# Uni-2_4.net
KiCad netlist of a schematic drawn in EAGLE
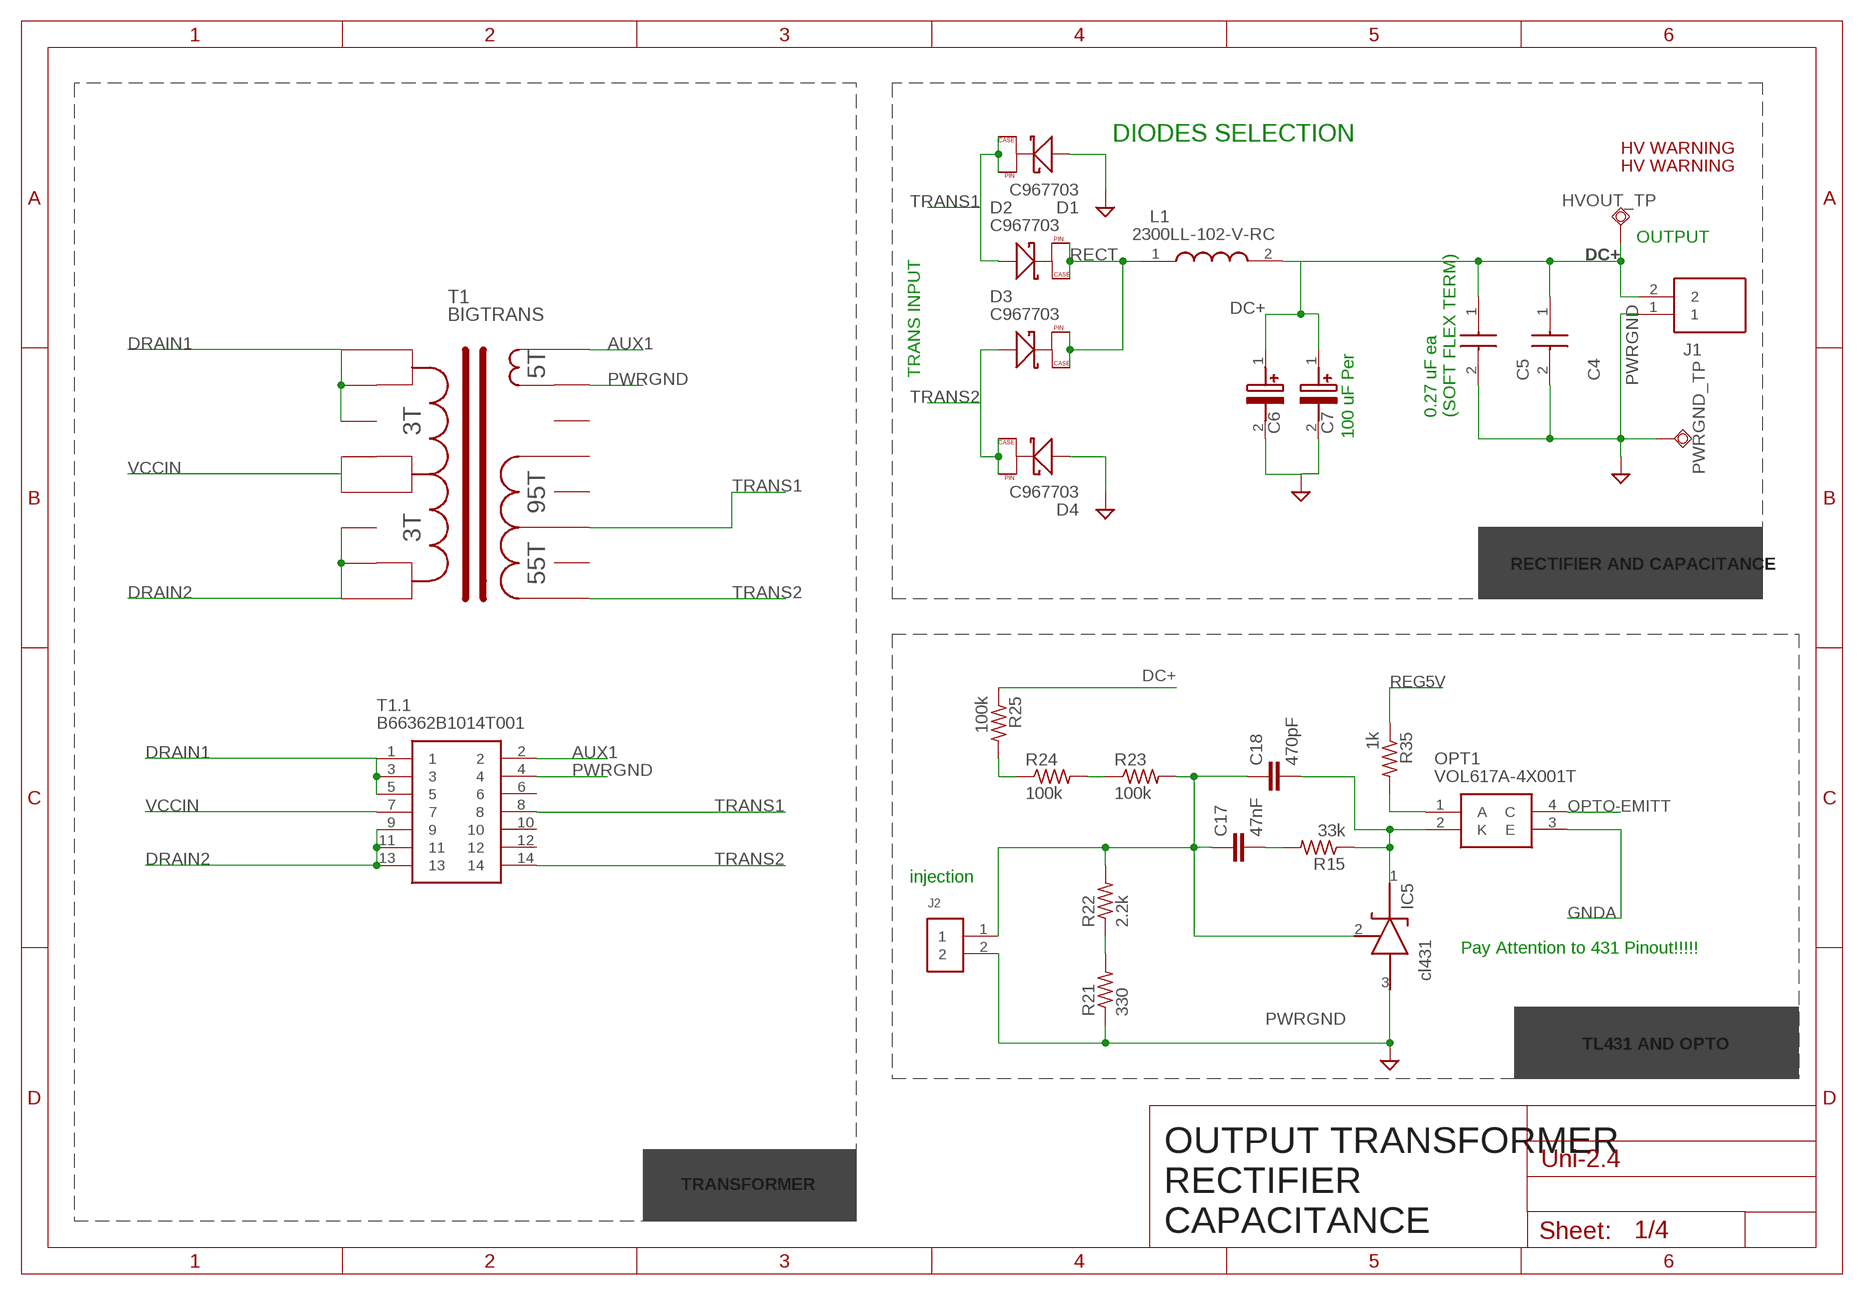
[diagram p0: schematic, sheet 1]
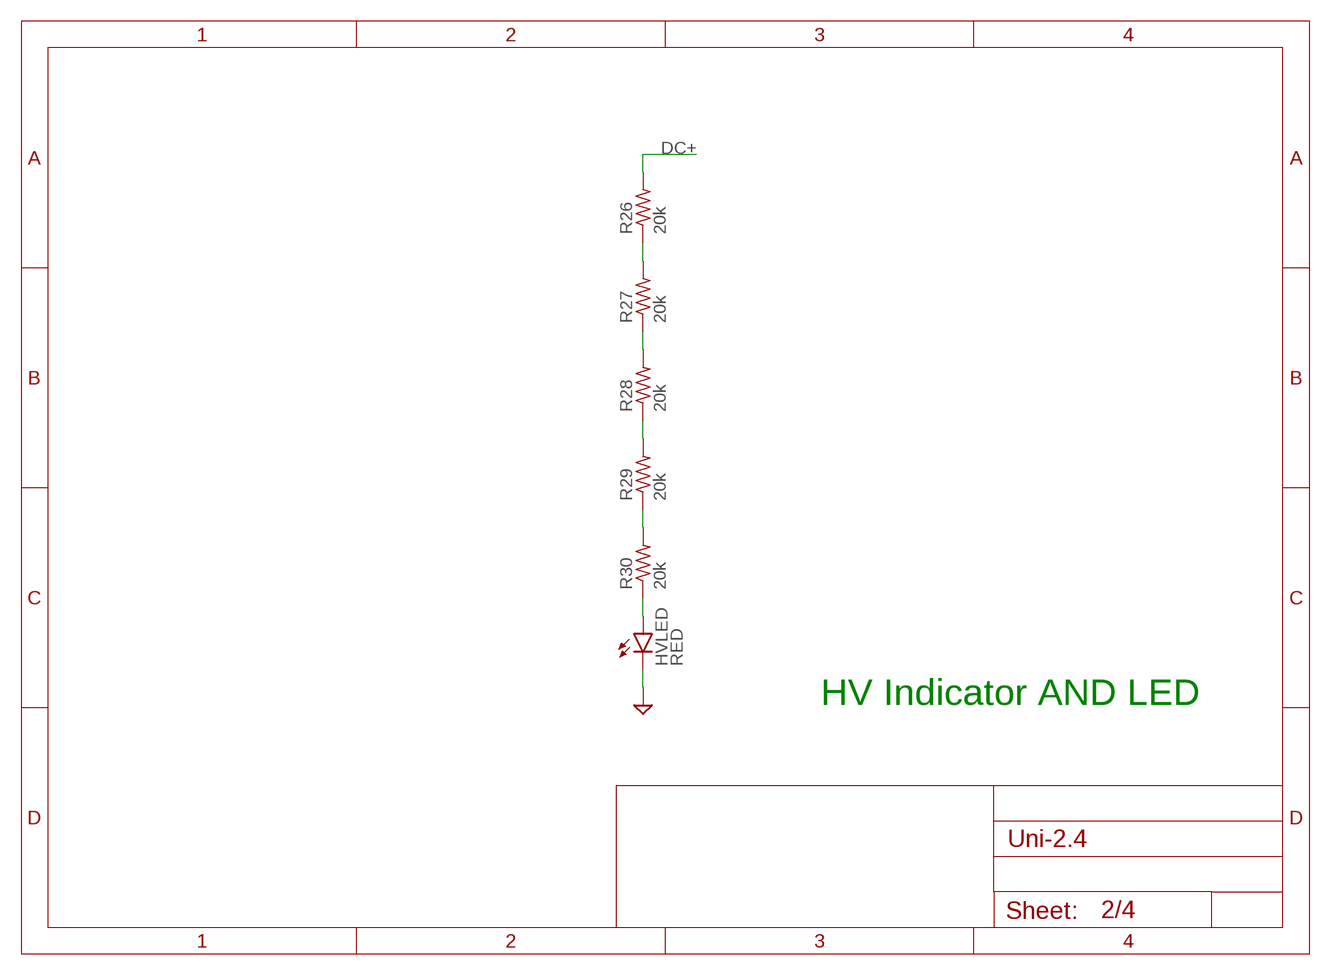
[diagram p1: schematic, sheet 2]
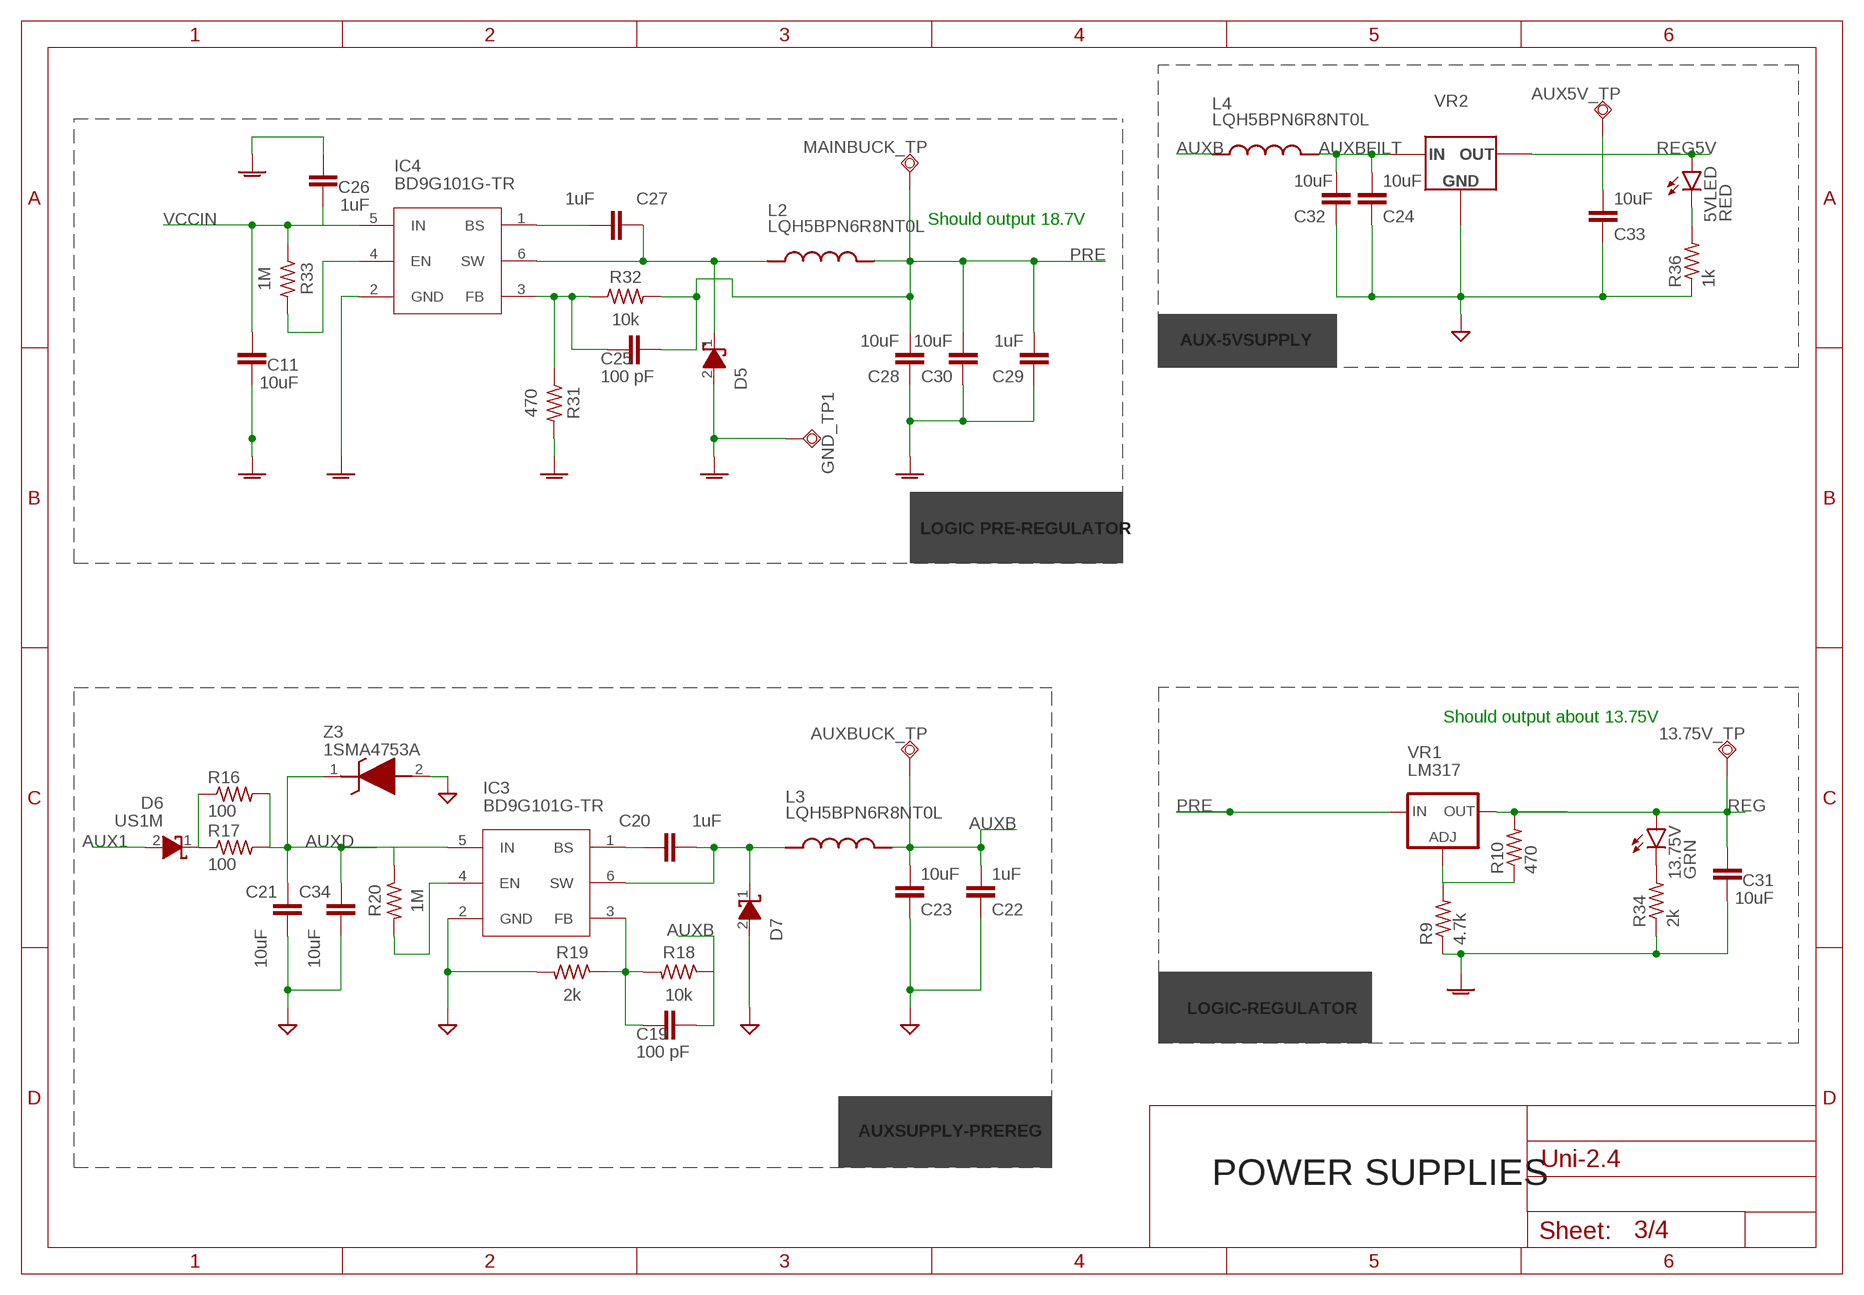
[diagram p2: schematic, sheet 3]
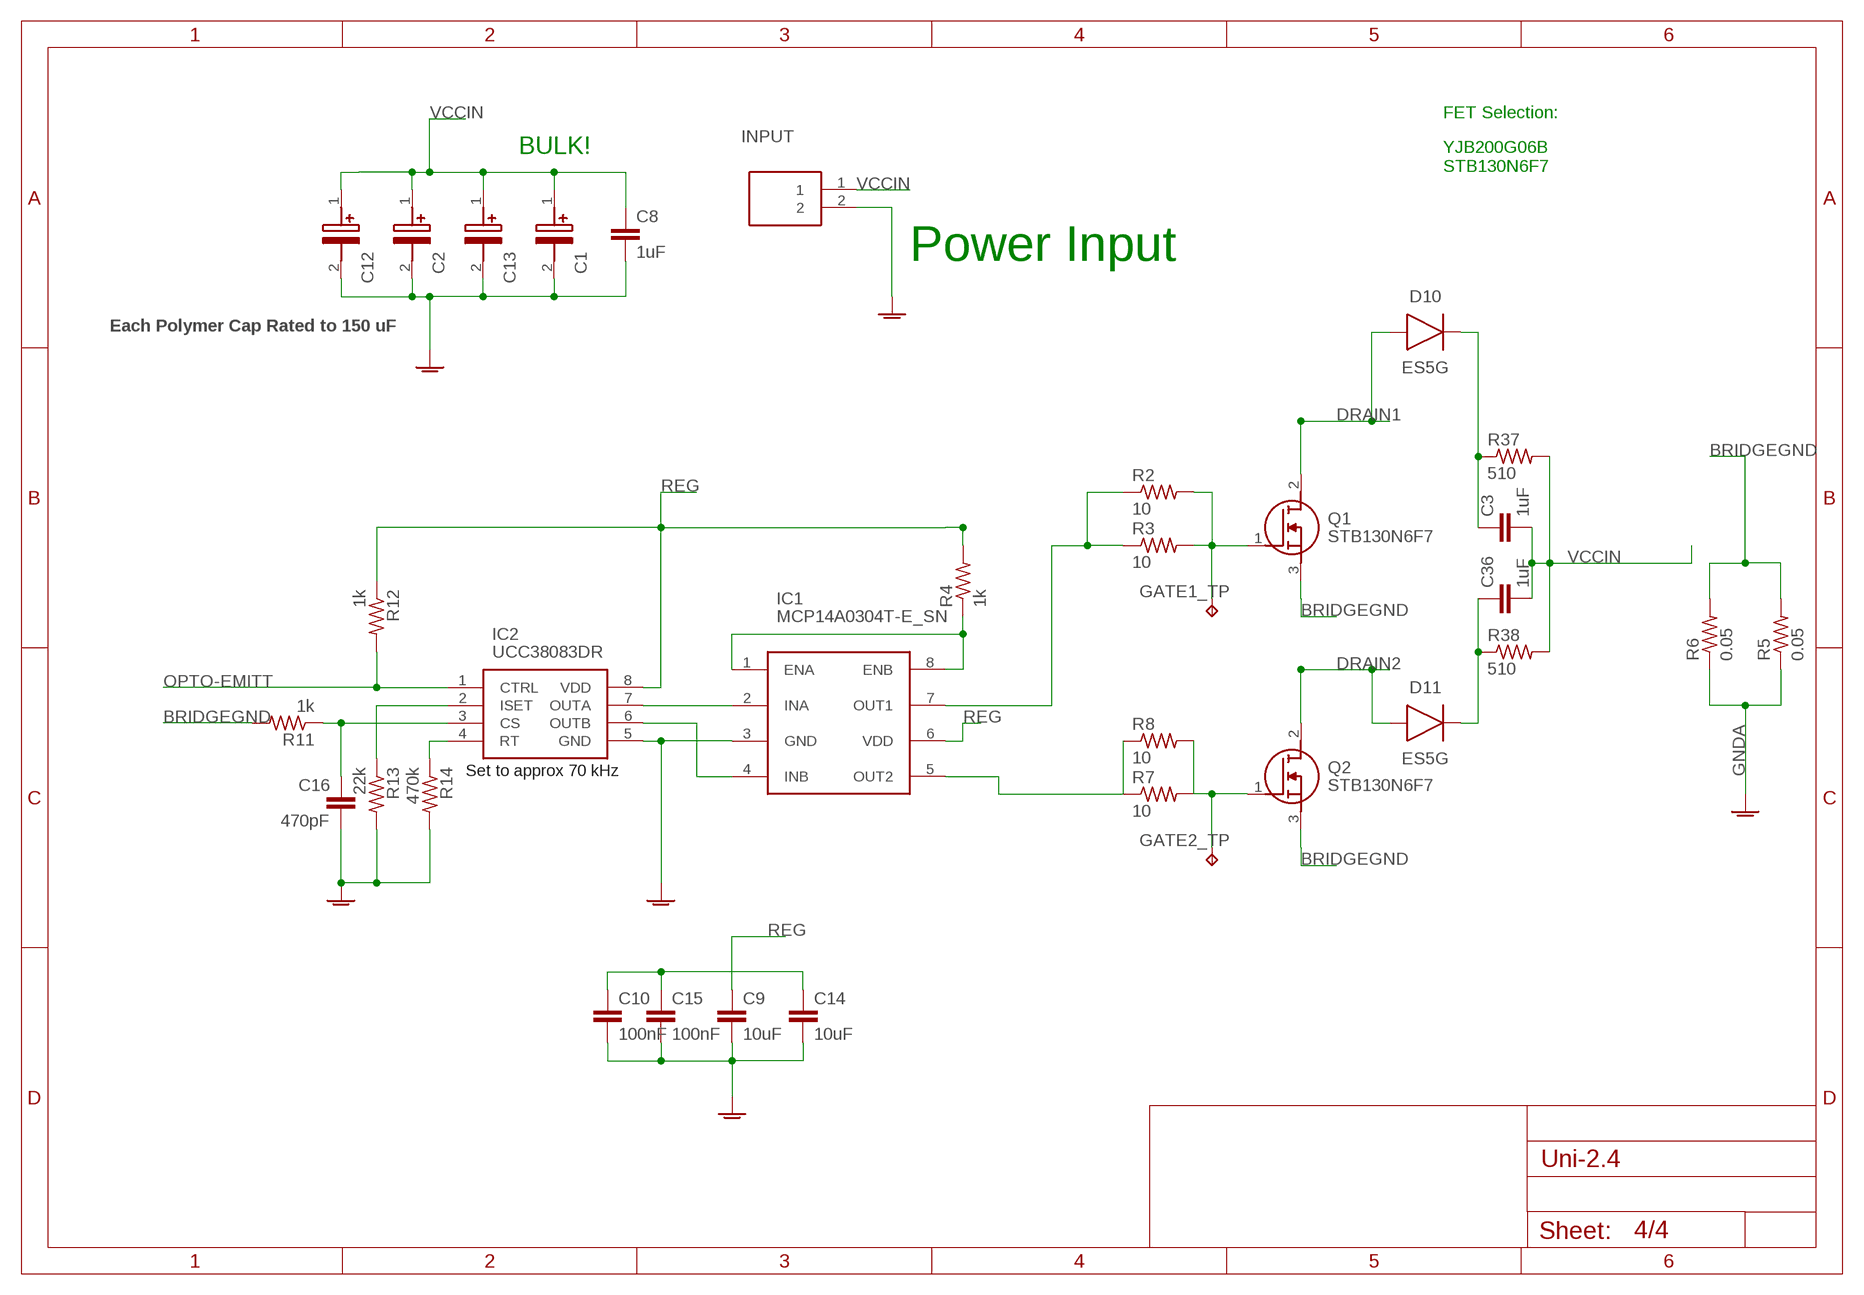
[diagram p3: schematic, sheet 4]

(export (version "E")
  (design (tool "Eeschema 10.0.6"))
  (components
    (comp (ref "HVLED")
      (value "RED")
      (footprint "eagle-import:CHIPLED_0805")
      (libsource (lib "eagle-import") (part "LEDCHIPLED_0805"))
    )
    (comp (ref "R26")
      (value "20k")
      (footprint "eagle-import:R1206")
      (libsource (lib "eagle-import") (part "R-US_R1206"))
    )
    (comp (ref "R27")
      (value "20k")
      (footprint "eagle-import:R1206")
      (libsource (lib "eagle-import") (part "R-US_R1206"))
    )
    (comp (ref "R28")
      (value "20k")
      (footprint "eagle-import:R1206")
      (libsource (lib "eagle-import") (part "R-US_R1206"))
    )
    (comp (ref "R29")
      (value "20k")
      (footprint "eagle-import:R1206")
      (libsource (lib "eagle-import") (part "R-US_R1206"))
    )
    (comp (ref "R30")
      (value "20k")
      (footprint "eagle-import:R1206")
      (libsource (lib "eagle-import") (part "R-US_R1206"))
    )
    (comp (ref "C4")
      (value "C1812C274KCRACAUTO")
      (footprint "eagle-import:C1812")
      (fields (field (name "MOUSER_PART_NUMBER") "80-C1812C274KCRAUTO"))
      (libsource (lib "eagle-import") (part "C1812C274KCRACAUTO"))
    )
    (comp (ref "C5")
      (value "C1812C274KCRACAUTO")
      (footprint "eagle-import:C1812")
      (fields (field (name "MOUSER_PART_NUMBER") "80-C1812C274KCRAUTO"))
      (libsource (lib "eagle-import") (part "C1812C274KCRACAUTO"))
    )
    (comp (ref "C6")
      (value "400BXW100MEFR18X25")
      (footprint "eagle-import:CAPPRD750W80D1825H2700")
      (libsource (lib "eagle-import") (part "400BXW100MEFR18X25"))
    )
    (comp (ref "C7")
      (value "400BXW100MEFR18X25")
      (footprint "eagle-import:CAPPRD750W80D1825H2700")
      (libsource (lib "eagle-import") (part "400BXW100MEFR18X25"))
    )
    (comp (ref "C17")
      (value "47nF")
      (footprint "eagle-import:C0603K")
      (libsource (lib "eagle-import") (part "rcl_334_C-EUC0603K"))
    )
    (comp (ref "C18")
      (value "470pF")
      (footprint "eagle-import:C0603K")
      (libsource (lib "eagle-import") (part "rcl_334_C-EUC0603K"))
    )
    (comp (ref "D1")
      (value "C967703")
      (footprint "eagle-import:TO-252")
      (libsource (lib "eagle-import") (part "SICDIODE"))
    )
    (comp (ref "D2")
      (value "C967703")
      (footprint "eagle-import:TO-252")
      (libsource (lib "eagle-import") (part "SICDIODE"))
    )
    (comp (ref "D3")
      (value "C967703")
      (footprint "eagle-import:TO-252")
      (libsource (lib "eagle-import") (part "SICDIODE"))
    )
    (comp (ref "D4")
      (value "C967703")
      (footprint "eagle-import:TO-252")
      (libsource (lib "eagle-import") (part "SICDIODE"))
    )
    (comp (ref "HVOUT_TP")
      (value "TPSQPAD1-13")
      (footprint "eagle-import:P1-13")
      (libsource (lib "eagle-import") (part "TPSQPAD1-13"))
    )
    (comp (ref "IC5")
      (value "cl431")
      (footprint "eagle-import:SOT95P280X145-3N")
      (fields
        (field (name "MANUFACTURER_PART_NUMBER") "TL431CL3T")
        (field (name "MOUSER_PART_NUMBER") "511-TL431CL3T")
      )
      (libsource (lib "eagle-import") (part "TL431CL3T"))
    )
    (comp (ref "J1")
      (value "TB005-762-02BE")
      (footprint "eagle-import:TB00576202BE")
      (fields (field (name "MOUSER_PART_NUMBER") "490-TB005-762-02BE"))
      (libsource (lib "eagle-import") (part "TB005-762-02BE"))
    )
    (comp (ref "J2")
      (value "61300211121")
      (footprint "eagle-import:61300211121")
      (fields
        (field (name "DIGI_KEY_PART_NUMBER") "732-5315-ND")
        (field (name "MANUFACTURER") "Wurth Electronics Inc.")
        (field (name "CREATED_BY") "PCBLayout.com")
      )
      (libsource (lib "eagle-import") (part "61300211121"))
    )
    (comp (ref "L1")
      (value "2300LL-102-V-RC")
      (footprint "eagle-import:2300LL102VRC")
      (fields (field (name "MOUSER_PART_NUMBER") "652-2300LL-102-V-RC"))
      (libsource (lib "eagle-import") (part "2300LL-102-V-RC"))
    )
    (comp (ref "OPT1")
      (value "VOL617A-4X001T")
      (footprint "eagle-import:SOP254P1015X230-4N")
      (fields (field (name "MOUSER_PART_NUMBER") "78-VOL617A-4X001T"))
      (libsource (lib "eagle-import") (part "VOL617A-4X001T"))
    )
    (comp (ref "PWRGND_TP")
      (value "TPSQPAD1-13")
      (footprint "eagle-import:P1-13")
      (libsource (lib "eagle-import") (part "TPSQPAD1-13"))
    )
    (comp (ref "R15")
      (value "33k")
      (footprint "eagle-import:R0603")
      (libsource (lib "eagle-import") (part "R-US_R0603"))
    )
    (comp (ref "R21")
      (value "330")
      (footprint "eagle-import:R0805")
      (libsource (lib "eagle-import") (part "R-US_R0805"))
    )
    (comp (ref "R22")
      (value "2.2k")
      (footprint "eagle-import:R0805")
      (libsource (lib "eagle-import") (part "R-US_R0805"))
    )
    (comp (ref "R23")
      (value "100k")
      (footprint "eagle-import:R1206")
      (libsource (lib "eagle-import") (part "R-US_R1206"))
    )
    (comp (ref "R24")
      (value "100k")
      (footprint "eagle-import:R1206")
      (libsource (lib "eagle-import") (part "R-US_R1206"))
    )
    (comp (ref "R25")
      (value "100k")
      (footprint "eagle-import:R1206")
      (libsource (lib "eagle-import") (part "R-US_R1206"))
    )
    (comp (ref "R35")
      (value "1k")
      (footprint "eagle-import:R0603")
      (libsource (lib "eagle-import") (part "R-US_R0603"))
    )
    (comp (ref "T1")
      (value "BIGTRANS")
      (footprint "eagle-import:BIGTRANS!")
      (libsource (lib "eagle-import") (part "BIGTRANS"))
    )
    (comp (ref "T1.1")
      (value "B66362B1014T001")
      (footprint "eagle-import:B66362B1014T001")
      (fields (field (name "MOUSER_PART_NUMBER") "871-B66362B1014T001"))
      (libsource (lib "eagle-import") (part "B66362B1014T001"))
    )
    (comp (ref "U$3")
      (value "HV")
      (footprint "eagle-import:PSFBC_ELECTRIC_SHOCK")
      (libsource (lib "eagle-import") (part "HV"))
    )
    (comp (ref "U$4")
      (value "HV")
      (footprint "eagle-import:PSFBC_ELECTRIC_SHOCK")
      (libsource (lib "eagle-import") (part "HV"))
    )
    (comp (ref "5VLED")
      (value "RED")
      (footprint "eagle-import:CHIPLED_0805")
      (fields (field (name "LCSC_PART") "C72043"))
      (libsource (lib "eagle-import") (part "LEDCHIPLED_0805"))
    )
    (comp (ref "13.75V")
      (value "GRN")
      (footprint "eagle-import:CHIPLED_0805")
      (fields (field (name "LCSC_PART") "C72043"))
      (libsource (lib "eagle-import") (part "LEDCHIPLED_0805"))
    )
    (comp (ref "13.75V_TP")
      (value "TPSQPAD1-17")
      (footprint "eagle-import:P1-17")
      (libsource (lib "eagle-import") (part "TPSQPAD1-17"))
    )
    (comp (ref "AUX5V_TP")
      (value "TPSQPAD1-17")
      (footprint "eagle-import:P1-17")
      (libsource (lib "eagle-import") (part "TPSQPAD1-17"))
    )
    (comp (ref "AUXBUCK_TP")
      (value "TPSQPAD1-17")
      (footprint "eagle-import:P1-17")
      (libsource (lib "eagle-import") (part "TPSQPAD1-17"))
    )
    (comp (ref "C11")
      (value "10uF")
      (footprint "eagle-import:C0805K")
      (fields (field (name "LCSC_PART") "C440198"))
      (libsource (lib "eagle-import") (part "C-EUC0805K"))
    )
    (comp (ref "C19")
      (value "100 pF")
      (footprint "eagle-import:C0402K")
      (fields (field (name "LCSC_PART") "C1546"))
      (libsource (lib "eagle-import") (part "rcl_334_C-EUC0402K"))
    )
    (comp (ref "C20")
      (value "1uF")
      (footprint "eagle-import:C0603K")
      (fields (field (name "LCSC_PART") "C14663"))
      (libsource (lib "eagle-import") (part "rcl_334_C-EUC0603K"))
    )
    (comp (ref "C21")
      (value "10uF")
      (footprint "eagle-import:C0805K")
      (libsource (lib "eagle-import") (part "rcl_334_C-EUC0805K"))
    )
    (comp (ref "C22")
      (value "1uF")
      (footprint "eagle-import:C0402")
      (fields (field (name "LCSC_PART") "C440198"))
      (libsource (lib "eagle-import") (part "rcl_334_C-EUC0402"))
    )
    (comp (ref "C23")
      (value "10uF")
      (footprint "eagle-import:C0603K")
      (fields (field (name "LCSC_PART") "C440198"))
      (libsource (lib "eagle-import") (part "rcl_334_C-EUC0603K"))
    )
    (comp (ref "C24")
      (value "10uF")
      (footprint "eagle-import:C0603K")
      (fields (field (name "LCSC_PART") "C440198"))
      (libsource (lib "eagle-import") (part "rcl_334_C-EUC0603K"))
    )
    (comp (ref "C25")
      (value "100 pF")
      (footprint "eagle-import:C0402K")
      (fields (field (name "LCSC_PART") "C1546"))
      (libsource (lib "eagle-import") (part "rcl_334_C-EUC0402K"))
    )
    (comp (ref "C26")
      (value "1uF")
      (footprint "eagle-import:C0603K")
      (fields (field (name "LCSC_PART") "C440198"))
      (libsource (lib "eagle-import") (part "rcl_334_C-EUC0603K"))
    )
    (comp (ref "C27")
      (value "1uF")
      (footprint "eagle-import:C0603K")
      (fields (field (name "LCSC_PART") "C14663"))
      (libsource (lib "eagle-import") (part "rcl_334_C-EUC0603K"))
    )
    (comp (ref "C28")
      (value "10uF")
      (footprint "eagle-import:C0603K")
      (fields (field (name "LCSC_PART") "C440198"))
      (libsource (lib "eagle-import") (part "C-EUC0603K"))
    )
    (comp (ref "C29")
      (value "1uF")
      (footprint "eagle-import:C0603K")
      (fields (field (name "LCSC_PART") "C440198"))
      (libsource (lib "eagle-import") (part "C-EUC0603K"))
    )
    (comp (ref "C30")
      (value "10uF")
      (footprint "eagle-import:C0603K")
      (fields (field (name "LCSC_PART") "C440198"))
      (libsource (lib "eagle-import") (part "C-EUC0603K"))
    )
    (comp (ref "C31")
      (value "10uF")
      (footprint "eagle-import:C0603K")
      (fields (field (name "LCSC_PART") "C440198"))
      (libsource (lib "eagle-import") (part "C-EUC0603K"))
    )
    (comp (ref "C32")
      (value "10uF")
      (footprint "eagle-import:C0603K")
      (fields (field (name "LCSC_PART") "C440198"))
      (libsource (lib "eagle-import") (part "rcl_334_C-EUC0603K"))
    )
    (comp (ref "C33")
      (value "10uF")
      (footprint "eagle-import:C0603K")
      (libsource (lib "eagle-import") (part "rcl_334_C-EUC0603K"))
    )
    (comp (ref "C34")
      (value "10uF")
      (footprint "eagle-import:C0805K")
      (libsource (lib "eagle-import") (part "rcl_334_C-EUC0805K"))
    )
    (comp (ref "D5")
      (value "SCHOTTKY")
      (footprint "eagle-import:DIOM5127X229N")
      (fields
        (field (name "MANUFACTURER_PART_NUMBER") "SS16HE3_B/H")
        (field (name "MOUSER_PART_NUMBER") "78-SS16HE3_B/H")
        (field (name "LCSC_PART") "C22452")
      )
      (libsource (lib "eagle-import") (part "SCHOTTKY"))
    )
    (comp (ref "D6")
      (value "US1M")
      (footprint "eagle-import:DIOM5127X229N")
      (fields
        (field (name "MANUFACTURER_PART_NUMBER") "SS16HE3_B/H")
        (field (name "MOUSER_PART_NUMBER") "78-SS16HE3_B/H")
      )
      (libsource (lib "eagle-import") (part "SCHOTTKY"))
    )
    (comp (ref "D7")
      (value "SCHOTTKY")
      (footprint "eagle-import:DIOM5127X229N")
      (fields
        (field (name "MANUFACTURER_PART_NUMBER") "SS16HE3_B/H")
        (field (name "MOUSER_PART_NUMBER") "78-SS16HE3_B/H")
        (field (name "LCSC_PART") "C22452")
      )
      (libsource (lib "eagle-import") (part "SCHOTTKY"))
    )
    (comp (ref "GND_TP1")
      (value "TPSQPAD1-13")
      (footprint "eagle-import:P1-13")
      (libsource (lib "eagle-import") (part "TPSQPAD1-13"))
    )
    (comp (ref "IC3")
      (value "BD9G101G-TR")
      (footprint "eagle-import:SOT95P280X145-6N")
      (fields (field (name "LCSC_PART") "C97643"))
      (libsource (lib "eagle-import") (part "BD9G101G-TR"))
    )
    (comp (ref "IC4")
      (value "BD9G101G-TR")
      (footprint "eagle-import:SOT95P280X145-6N")
      (fields (field (name "LCSC_PART") "C97643"))
      (libsource (lib "eagle-import") (part "BD9G101G-TR"))
    )
    (comp (ref "L2")
      (value "LQH5BPN6R8NT0L")
      (footprint "eagle-import:LQH5BPB100MT0L")
      (fields (field (name "MOUSER_PART_NUMBER") "81-LQH5BPN6R8NT0L0L"))
      (libsource (lib "eagle-import") (part "LQH5BPN6R8NT0L"))
    )
    (comp (ref "L3")
      (value "LQH5BPN6R8NT0L")
      (footprint "eagle-import:LQH5BPB100MT0L")
      (fields (field (name "MOUSER_PART_NUMBER") "81-LQH5BPN6R8NT0L0L"))
      (libsource (lib "eagle-import") (part "LQH5BPN6R8NT0L"))
    )
    (comp (ref "L4")
      (value "LQH5BPN6R8NT0L")
      (footprint "eagle-import:LQH5BPB100MT0L")
      (fields (field (name "MOUSER_PART_NUMBER") "81-LQH5BPN6R8NT0L0L"))
      (libsource (lib "eagle-import") (part "LQH5BPN6R8NT0L"))
    )
    (comp (ref "MAINBUCK_TP")
      (value "TPSQPAD1-17")
      (footprint "eagle-import:P1-17")
      (libsource (lib "eagle-import") (part "TPSQPAD1-17"))
    )
    (comp (ref "R9")
      (value "4.7k")
      (footprint "eagle-import:R0603")
      (fields (field (name "LCSC_PART") "C22975"))
      (libsource (lib "eagle-import") (part "R-US_R0603"))
    )
    (comp (ref "R10")
      (value "470")
      (footprint "eagle-import:R0603")
      (fields (field (name "LCSC_PART") "C22975"))
      (libsource (lib "eagle-import") (part "R-US_R0603"))
    )
    (comp (ref "R16")
      (value "100")
      (footprint "eagle-import:R1206")
      (libsource (lib "eagle-import") (part "R-US_R1206"))
    )
    (comp (ref "R17")
      (value "100")
      (footprint "eagle-import:R1206")
      (libsource (lib "eagle-import") (part "R-US_R1206"))
    )
    (comp (ref "R18")
      (value "10k")
      (footprint "eagle-import:R0402")
      (fields (field (name "LCSC_PART") "C25779"))
      (libsource (lib "eagle-import") (part "R-US_R0402"))
    )
    (comp (ref "R19")
      (value "2k")
      (footprint "eagle-import:R0402")
      (fields (field (name "LCSC_PART") "C25779"))
      (libsource (lib "eagle-import") (part "R-US_R0402"))
    )
    (comp (ref "R20")
      (value "1M")
      (footprint "eagle-import:R0402")
      (fields (field (name "LCSC_PART") "C25741") (field (name "SPICEPREFIX") "R"))
      (libsource (lib "eagle-import") (part "R-US_R0402"))
    )
    (comp (ref "R31")
      (value "470")
      (footprint "eagle-import:R0603")
      (fields (field (name "LCSC_PART") "C4177") (field (name "SPICEPREFIX") "R"))
      (libsource (lib "eagle-import") (part "R-US_R0603"))
    )
    (comp (ref "R32")
      (value "10k")
      (footprint "eagle-import:R0402")
      (fields (field (name "LCSC_PART") "C25779"))
      (libsource (lib "eagle-import") (part "R-US_R0402"))
    )
    (comp (ref "R33")
      (value "1M")
      (footprint "eagle-import:R0402")
      (fields (field (name "LCSC_PART") "C25741") (field (name "SPICEPREFIX") "R"))
      (libsource (lib "eagle-import") (part "R-US_R0402"))
    )
    (comp (ref "R34")
      (value "2k")
      (footprint "eagle-import:R0603")
      (fields (field (name "LCSC_PART") "C22975"))
      (libsource (lib "eagle-import") (part "R-US_R0603"))
    )
    (comp (ref "R36")
      (value "1k")
      (footprint "eagle-import:R0603")
      (fields (field (name "LCSC_PART") "C22975"))
      (libsource (lib "eagle-import") (part "R-US_R0603"))
    )
    (comp (ref "VR1")
      (value "LM317")
      (footprint "eagle-import:DPACK")
      (libsource (lib "eagle-import") (part "LM317?MBDT"))
    )
    (comp (ref "VR2")
      (value "AP2120N-5.0TRG1")
      (footprint "eagle-import:SOT95P280X145-3N")
      (fields (field (name "MOUSER_PART_NUMBER") "621-AP2120N-5.0TRG1"))
      (libsource (lib "eagle-import") (part "AP2120N-5.0TRG1"))
    )
    (comp (ref "Z3")
      (value "1SMA4753A")
      (footprint "eagle-import:DIOM5226X220N")
      (fields
        (field (name "MANUFACTURER_PART_NUMBER") "1SMA5942BT3G")
        (field (name "MOUSER_PART_NUMBER") "863-1SMA5942BT3G")
        (field (name "LCSC_PART") "C362284")
      )
      (libsource (lib "eagle-import") (part "1SMA5942BT3G"))
    )
    (comp (ref "C1")
      (value "OVK151M1VTR-10131")
      (footprint "eagle-import:16SVF1000M")
      (libsource (lib "eagle-import") (part "OVK151M1VTR-10131"))
    )
    (comp (ref "C2")
      (value "OVK151M1VTR-10131")
      (footprint "eagle-import:16SVF1000M")
      (libsource (lib "eagle-import") (part "OVK151M1VTR-10131"))
    )
    (comp (ref "C3")
      (value "1uF")
      (footprint "eagle-import:C1206K")
      (libsource (lib "eagle-import") (part "rcl_334_C-EUC1206K"))
    )
    (comp (ref "C8")
      (value "1uF")
      (footprint "eagle-import:C0805K")
      (fields (field (name "LCSC_PART") "C440198"))
      (libsource (lib "eagle-import") (part "rcl_334_C-EUC0805K"))
    )
    (comp (ref "C9")
      (value "10uF")
      (footprint "eagle-import:C0603K")
      (fields (field (name "LCSC_PART") "C440198"))
      (libsource (lib "eagle-import") (part "rcl_334_C-EUC0603K"))
    )
    (comp (ref "C10")
      (value "100nF")
      (footprint "eagle-import:C0402")
      (fields (field (name "LCSC_PART") "C440198"))
      (libsource (lib "eagle-import") (part "rcl_334_C-EUC0402"))
    )
    (comp (ref "C12")
      (value "OVK151M1VTR-10131")
      (footprint "eagle-import:16SVF1000M")
      (libsource (lib "eagle-import") (part "OVK151M1VTR-10131"))
    )
    (comp (ref "C13")
      (value "OVK151M1VTR-10131")
      (footprint "eagle-import:16SVF1000M")
      (libsource (lib "eagle-import") (part "OVK151M1VTR-10131"))
    )
    (comp (ref "C14")
      (value "10uF")
      (footprint "eagle-import:C0603K")
      (fields (field (name "LCSC_PART") "C440198"))
      (libsource (lib "eagle-import") (part "rcl_334_C-EUC0603K"))
    )
    (comp (ref "C15")
      (value "100nF")
      (footprint "eagle-import:C0402")
      (fields (field (name "LCSC_PART") "C440198"))
      (libsource (lib "eagle-import") (part "rcl_334_C-EUC0402"))
    )
    (comp (ref "C16")
      (value "470pF")
      (footprint "eagle-import:C0603K")
      (fields (field (name "LCSC_PART") "C1620"))
      (libsource (lib "eagle-import") (part "rcl_334_C-EUC0603K"))
    )
    (comp (ref "C36")
      (value "1uF")
      (footprint "eagle-import:C1206K")
      (libsource (lib "eagle-import") (part "rcl_334_C-EUC1206K"))
    )
    (comp (ref "D10")
      (value "ES5G")
      (footprint "eagle-import:DIOM5336X265N")
      (fields (field (name "LCSC_PART") "C128705"))
      (libsource (lib "eagle-import") (part "DIODEDO-214AA(SMB)"))
    )
    (comp (ref "D11")
      (value "ES5G")
      (footprint "eagle-import:DIOM5336X265N")
      (libsource (lib "eagle-import") (part "DIODEDO-214AA(SMB)"))
    )
    (comp (ref "GATE1_TP")
      (value "TPTP13R")
      (footprint "eagle-import:TP13R")
      (libsource (lib "eagle-import") (part "TPTP13R"))
    )
    (comp (ref "GATE2_TP")
      (value "TPTP13R")
      (footprint "eagle-import:TP13R")
      (libsource (lib "eagle-import") (part "TPTP13R"))
    )
    (comp (ref "IC1")
      (value "MCP14A0304T-E_SN")
      (footprint "eagle-import:SOIC127P600X175-8N")
      (fields
        (field (name "MANUFACTURER_PART_NUMBER") "MCP14A0304T-E/SN")
        (field (name "MOUSER_PART_NUMBER") "579-MCP14A0304T-E/SN")
      )
      (libsource (lib "eagle-import") (part "MCP14A0304T-E_SN"))
    )
    (comp (ref "IC2")
      (value "UCC38083DR")
      (footprint "eagle-import:SOIC127P600X175-8N")
      (fields (field (name "MOUSER_PART_NUMBER") "595-UCC38083DR"))
      (libsource (lib "eagle-import") (part "UCC38083DR"))
    )
    (comp (ref "INPUT")
      (value "TB005-762-02BE")
      (footprint "eagle-import:TB00576202BE")
      (fields (field (name "MOUSER_PART_NUMBER") "490-TB005-762-02BE"))
      (libsource (lib "eagle-import") (part "TB005-762-02BE"))
    )
    (comp (ref "Q1")
      (value "STB130N6F7")
      (footprint "eagle-import:D2PAK")
      (libsource (lib "eagle-import") (part "STB130N6F7"))
    )
    (comp (ref "Q2")
      (value "STB130N6F7")
      (footprint "eagle-import:D2PAK")
      (libsource (lib "eagle-import") (part "STB130N6F7"))
    )
    (comp (ref "R2")
      (value "10")
      (footprint "eagle-import:R0805")
      (libsource (lib "eagle-import") (part "R-US_R0805"))
    )
    (comp (ref "R3")
      (value "10")
      (footprint "eagle-import:R0805")
      (libsource (lib "eagle-import") (part "R-US_R0805"))
    )
    (comp (ref "R4")
      (value "1k")
      (footprint "eagle-import:R0402")
      (libsource (lib "eagle-import") (part "R-US_R0402"))
    )
    (comp (ref "R5")
      (value "0.05")
      (footprint "eagle-import:R2512")
      (libsource (lib "eagle-import") (part "R-US_R2512"))
    )
    (comp (ref "R6")
      (value "0.05")
      (footprint "eagle-import:R2512")
      (libsource (lib "eagle-import") (part "R-US_R2512"))
    )
    (comp (ref "R7")
      (value "10")
      (footprint "eagle-import:R0805")
      (libsource (lib "eagle-import") (part "R-US_R0805"))
    )
    (comp (ref "R8")
      (value "10")
      (footprint "eagle-import:R0805")
      (libsource (lib "eagle-import") (part "R-US_R0805"))
    )
    (comp (ref "R11")
      (value "1k")
      (footprint "eagle-import:R0603")
      (fields (field (name "LCSC_PART") "C21190"))
      (libsource (lib "eagle-import") (part "R-US_R0603"))
    )
    (comp (ref "R12")
      (value "1k")
      (footprint "eagle-import:R0603")
      (fields (field (name "LCSC_PART") "C22975"))
      (libsource (lib "eagle-import") (part "R-US_R0603"))
    )
    (comp (ref "R13")
      (value "22k")
      (footprint "eagle-import:R0603")
      (fields (field (name "LCSC_PART") "C31850"))
      (libsource (lib "eagle-import") (part "R-US_R0603"))
    )
    (comp (ref "R14")
      (value "470k")
      (footprint "eagle-import:R0603")
      (fields (field (name "LCSC_PART") "C25811"))
      (libsource (lib "eagle-import") (part "R-US_R0603"))
    )
    (comp (ref "R37")
      (value "510")
      (footprint "eagle-import:R2512")
      (libsource (lib "eagle-import") (part "R-US_R2512"))
    )
    (comp (ref "R38")
      (value "510")
      (footprint "eagle-import:R2512")
      (libsource (lib "eagle-import") (part "R-US_R2512"))
    )
  )
  (nets
    (net (code "1") (name "AUX1") (class "Default")
      (node (ref "D6") (pin "2") (pinfunction "A_2") (pintype "bidirectional"))
      (node (ref "T1") (pin "16") (pinfunction "16_16") (pintype "bidirectional"))
      (node (ref "T1.1") (pin "2") (pinfunction "2_2") (pintype "bidirectional"))
    )
    (net (code "2") (name "AUXB") (class "Default")
      (node (ref "AUXBUCK_TP") (pin "TP") (pinfunction "TP_TP") (pintype "input"))
      (node (ref "C19") (pin "1") (pinfunction "1_1") (pintype "passive"))
      (node (ref "C22") (pin "2") (pinfunction "2_2") (pintype "passive"))
      (node (ref "C23") (pin "2") (pinfunction "2_2") (pintype "passive"))
      (node (ref "L3") (pin "2") (pinfunction "P$2_2") (pintype "bidirectional"))
      (node (ref "L4") (pin "1") (pinfunction "P$1_1") (pintype "bidirectional"))
      (node (ref "R18") (pin "1") (pinfunction "1_1") (pintype "passive"))
    )
    (net (code "3") (name "AUXBFILT") (class "Default")
      (node (ref "C24") (pin "2") (pinfunction "2_2") (pintype "passive"))
      (node (ref "C32") (pin "2") (pinfunction "2_2") (pintype "passive"))
      (node (ref "L4") (pin "2") (pinfunction "P$2_2") (pintype "bidirectional"))
      (node (ref "VR2") (pin "3") (pinfunction "VIN_3") (pintype "bidirectional"))
    )
    (net (code "4") (name "AUXD") (class "Default")
      (node (ref "C21") (pin "1") (pinfunction "1_1") (pintype "passive"))
      (node (ref "C34") (pin "1") (pinfunction "1_1") (pintype "passive"))
      (node (ref "IC3") (pin "5") (pinfunction "IN_5") (pintype "bidirectional"))
      (node (ref "R16") (pin "2") (pinfunction "2_2") (pintype "passive"))
      (node (ref "R17") (pin "2") (pinfunction "2_2") (pintype "passive"))
      (node (ref "R20") (pin "1") (pinfunction "1_1") (pintype "passive"))
      (node (ref "Z3") (pin "1") (pinfunction "K_1") (pintype "bidirectional"))
    )
    (net (code "5") (name "BRIDGEGND") (class "Default")
      (node (ref "Q1") (pin "3") (pinfunction "S_3") (pintype "bidirectional"))
      (node (ref "Q2") (pin "3") (pinfunction "S_3") (pintype "bidirectional"))
      (node (ref "R11") (pin "2") (pinfunction "2_2") (pintype "passive"))
      (node (ref "R5") (pin "2") (pinfunction "2_2") (pintype "passive"))
      (node (ref "R6") (pin "2") (pinfunction "2_2") (pintype "passive"))
    )
    (net (code "6") (name "DC+") (class "Default")
      (node (ref "C4") (pin "1") (pinfunction "1_1") (pintype "bidirectional"))
      (node (ref "C5") (pin "1") (pinfunction "1_1") (pintype "bidirectional"))
      (node (ref "C6") (pin "1") (pinfunction "+_1") (pintype "bidirectional"))
      (node (ref "C7") (pin "1") (pinfunction "+_1") (pintype "bidirectional"))
      (node (ref "HVOUT_TP") (pin "TP") (pinfunction "TP_TP") (pintype "input"))
      (node (ref "J1") (pin "2") (pinfunction "2_2") (pintype "bidirectional"))
      (node (ref "L1") (pin "2") (pinfunction "2_2") (pintype "bidirectional"))
      (node (ref "R25") (pin "1") (pinfunction "1_1") (pintype "passive"))
      (node (ref "R26") (pin "2") (pinfunction "2_2") (pintype "passive"))
    )
    (net (code "7") (name "DRAIN1") (class "Default")
      (node (ref "D10") (pin "2") (pinfunction "A_2") (pintype "passive"))
      (node (ref "Q1") (pin "2") (pinfunction "D_2") (pintype "bidirectional"))
      (node (ref "T1") (pin "6") (pinfunction "6_6") (pintype "bidirectional"))
      (node (ref "T1") (pin "7") (pinfunction "7_7") (pintype "bidirectional"))
      (node (ref "T1") (pin "8") (pinfunction "8_8") (pintype "bidirectional"))
      (node (ref "T1.1") (pin "1") (pinfunction "1_1") (pintype "bidirectional"))
      (node (ref "T1.1") (pin "3") (pinfunction "3_3") (pintype "bidirectional"))
      (node (ref "T1.1") (pin "5") (pinfunction "5_5") (pintype "bidirectional"))
    )
    (net (code "8") (name "DRAIN2") (class "Default")
      (node (ref "D11") (pin "2") (pinfunction "A_2") (pintype "passive"))
      (node (ref "Q2") (pin "2") (pinfunction "D_2") (pintype "bidirectional"))
      (node (ref "T1") (pin "1") (pinfunction "1_1") (pintype "bidirectional"))
      (node (ref "T1") (pin "2") (pinfunction "2_2") (pintype "bidirectional"))
      (node (ref "T1") (pin "3") (pinfunction "3_3") (pintype "bidirectional"))
      (node (ref "T1.1") (pin "11") (pinfunction "11_11") (pintype "bidirectional"))
      (node (ref "T1.1") (pin "13") (pinfunction "13_13") (pintype "bidirectional"))
      (node (ref "T1.1") (pin "9") (pinfunction "9_9") (pintype "bidirectional"))
    )
    (net (code "9") (name "GNDA") (class "Default")
      (node (ref "C1") (pin "2") (pinfunction "-_2") (pintype "bidirectional"))
      (node (ref "C10") (pin "2") (pinfunction "2_2") (pintype "passive"))
      (node (ref "C11") (pin "1") (pinfunction "1_1") (pintype "passive"))
      (node (ref "C12") (pin "2") (pinfunction "-_2") (pintype "bidirectional"))
      (node (ref "C13") (pin "2") (pinfunction "-_2") (pintype "bidirectional"))
      (node (ref "C14") (pin "2") (pinfunction "2_2") (pintype "passive"))
      (node (ref "C15") (pin "2") (pinfunction "2_2") (pintype "passive"))
      (node (ref "C16") (pin "2") (pinfunction "2_2") (pintype "passive"))
      (node (ref "C2") (pin "2") (pinfunction "-_2") (pintype "bidirectional"))
      (node (ref "C26") (pin "2") (pinfunction "2_2") (pintype "passive"))
      (node (ref "C28") (pin "1") (pinfunction "1_1") (pintype "passive"))
      (node (ref "C29") (pin "1") (pinfunction "1_1") (pintype "passive"))
      (node (ref "C30") (pin "1") (pinfunction "1_1") (pintype "passive"))
      (node (ref "C31") (pin "1") (pinfunction "1_1") (pintype "passive"))
      (node (ref "C8") (pin "2") (pinfunction "2_2") (pintype "passive"))
      (node (ref "C9") (pin "2") (pinfunction "2_2") (pintype "passive"))
      (node (ref "D5") (pin "2") (pinfunction "A_2") (pintype "bidirectional"))
      (node (ref "GND_TP1") (pin "TP") (pinfunction "TP_TP") (pintype "input"))
      (node (ref "IC1") (pin "3") (pinfunction "GND_3") (pintype "bidirectional"))
      (node (ref "IC2") (pin "5") (pinfunction "GND_5") (pintype "bidirectional"))
      (node (ref "IC4") (pin "2") (pinfunction "GND_2") (pintype "bidirectional"))
      (node (ref "INPUT") (pin "2") (pinfunction "2_2") (pintype "bidirectional"))
      (node (ref "OPT1") (pin "3") (pinfunction "E_3") (pintype "bidirectional"))
      (node (ref "R13") (pin "2") (pinfunction "2_2") (pintype "passive"))
      (node (ref "R14") (pin "2") (pinfunction "2_2") (pintype "passive"))
      (node (ref "R31") (pin "2") (pinfunction "2_2") (pintype "passive"))
      (node (ref "R34") (pin "1") (pinfunction "1_1") (pintype "passive"))
      (node (ref "R5") (pin "1") (pinfunction "1_1") (pintype "passive"))
      (node (ref "R6") (pin "1") (pinfunction "1_1") (pintype "passive"))
      (node (ref "R9") (pin "1") (pinfunction "1_1") (pintype "passive"))
    )
    (net (code "10") (name "Net-(5VLED-PadC)") (class "Default")
      (node (ref "5VLED") (pin "C") (pinfunction "C_C") (pintype "passive"))
      (node (ref "R36") (pin "2") (pinfunction "2_2") (pintype "passive"))
    )
    (net (code "11") (name "Net-(13.75V-PadC)") (class "Default")
      (node (ref "13.75V") (pin "C") (pinfunction "C_C") (pintype "passive"))
      (node (ref "R34") (pin "2") (pinfunction "2_2") (pintype "passive"))
    )
    (net (code "12") (name "Net-(C17-Pad2)") (class "Default")
      (node (ref "C17") (pin "2") (pinfunction "2_2") (pintype "passive"))
      (node (ref "R15") (pin "2") (pinfunction "2_2") (pintype "passive"))
    )
    (net (code "13") (name "Net-(D5-K)") (class "Default")
      (node (ref "C27") (pin "1") (pinfunction "1_1") (pintype "passive"))
      (node (ref "D5") (pin "1") (pinfunction "K_1") (pintype "bidirectional"))
      (node (ref "IC4") (pin "6") (pinfunction "SW_6") (pintype "bidirectional"))
      (node (ref "L2") (pin "1") (pinfunction "P$1_1") (pintype "bidirectional"))
    )
    (net (code "14") (name "Net-(D6-K)") (class "Default")
      (node (ref "D6") (pin "1") (pinfunction "K_1") (pintype "bidirectional"))
      (node (ref "R16") (pin "1") (pinfunction "1_1") (pintype "passive"))
      (node (ref "R17") (pin "1") (pinfunction "1_1") (pintype "passive"))
    )
    (net (code "15") (name "Net-(D7-K)") (class "Default")
      (node (ref "C20") (pin "2") (pinfunction "2_2") (pintype "passive"))
      (node (ref "D7") (pin "1") (pinfunction "K_1") (pintype "bidirectional"))
      (node (ref "IC3") (pin "6") (pinfunction "SW_6") (pintype "bidirectional"))
      (node (ref "L3") (pin "1") (pinfunction "P$1_1") (pintype "bidirectional"))
    )
    (net (code "16") (name "Net-(D10-C)") (class "Default")
      (node (ref "C3") (pin "1") (pinfunction "1_1") (pintype "passive"))
      (node (ref "D10") (pin "1") (pinfunction "C_1") (pintype "passive"))
      (node (ref "R37") (pin "1") (pinfunction "1_1") (pintype "passive"))
    )
    (net (code "17") (name "Net-(D11-C)") (class "Default")
      (node (ref "C36") (pin "1") (pinfunction "1_1") (pintype "passive"))
      (node (ref "D11") (pin "1") (pinfunction "C_1") (pintype "passive"))
      (node (ref "R38") (pin "1") (pinfunction "1_1") (pintype "passive"))
    )
    (net (code "18") (name "Net-(HVLED-PadA)") (class "Default")
      (node (ref "HVLED") (pin "A") (pinfunction "A_A") (pintype "passive"))
      (node (ref "R30") (pin "1") (pinfunction "1_1") (pintype "passive"))
    )
    (net (code "19") (name "Net-(IC1-ENA)") (class "Default")
      (node (ref "IC1") (pin "1") (pinfunction "ENA_1") (pintype "bidirectional"))
      (node (ref "IC1") (pin "8") (pinfunction "ENB_8") (pintype "bidirectional"))
      (node (ref "R4") (pin "1") (pinfunction "1_1") (pintype "passive"))
    )
    (net (code "20") (name "Net-(IC1-INA)") (class "Default")
      (node (ref "IC1") (pin "2") (pinfunction "INA_2") (pintype "bidirectional"))
      (node (ref "IC2") (pin "7") (pinfunction "OUTA_7") (pintype "bidirectional"))
    )
    (net (code "21") (name "Net-(IC1-INB)") (class "Default")
      (node (ref "IC1") (pin "4") (pinfunction "INB_4") (pintype "bidirectional"))
      (node (ref "IC2") (pin "6") (pinfunction "OUTB_6") (pintype "bidirectional"))
    )
    (net (code "22") (name "Net-(IC1-OUT1)") (class "Default")
      (node (ref "IC1") (pin "7") (pinfunction "OUT1_7") (pintype "bidirectional"))
      (node (ref "R2") (pin "1") (pinfunction "1_1") (pintype "passive"))
      (node (ref "R3") (pin "1") (pinfunction "1_1") (pintype "passive"))
    )
    (net (code "23") (name "Net-(IC1-OUT2)") (class "Default")
      (node (ref "IC1") (pin "5") (pinfunction "OUT2_5") (pintype "bidirectional"))
      (node (ref "R7") (pin "1") (pinfunction "1_1") (pintype "passive"))
      (node (ref "R8") (pin "1") (pinfunction "1_1") (pintype "passive"))
    )
    (net (code "24") (name "Net-(IC2-CS)") (class "Default")
      (node (ref "C16") (pin "1") (pinfunction "1_1") (pintype "passive"))
      (node (ref "IC2") (pin "3") (pinfunction "CS_3") (pintype "bidirectional"))
      (node (ref "R11") (pin "1") (pinfunction "1_1") (pintype "passive"))
    )
    (net (code "25") (name "Net-(IC2-ISET)") (class "Default")
      (node (ref "IC2") (pin "2") (pinfunction "ISET_2") (pintype "bidirectional"))
      (node (ref "R13") (pin "1") (pinfunction "1_1") (pintype "passive"))
    )
    (net (code "26") (name "Net-(IC2-RT)") (class "Default")
      (node (ref "IC2") (pin "4") (pinfunction "RT_4") (pintype "bidirectional"))
      (node (ref "R14") (pin "1") (pinfunction "1_1") (pintype "passive"))
    )
    (net (code "27") (name "Net-(IC3-BS)") (class "Default")
      (node (ref "C20") (pin "1") (pinfunction "1_1") (pintype "passive"))
      (node (ref "IC3") (pin "1") (pinfunction "BS_1") (pintype "bidirectional"))
    )
    (net (code "28") (name "Net-(IC3-EN)") (class "Default")
      (node (ref "IC3") (pin "4") (pinfunction "EN_4") (pintype "bidirectional"))
      (node (ref "R20") (pin "2") (pinfunction "2_2") (pintype "passive"))
    )
    (net (code "29") (name "Net-(IC3-FB)") (class "Default")
      (node (ref "C19") (pin "2") (pinfunction "2_2") (pintype "passive"))
      (node (ref "IC3") (pin "3") (pinfunction "FB_3") (pintype "bidirectional"))
      (node (ref "R18") (pin "2") (pinfunction "2_2") (pintype "passive"))
      (node (ref "R19") (pin "1") (pinfunction "1_1") (pintype "passive"))
    )
    (net (code "30") (name "Net-(IC4-BS)") (class "Default")
      (node (ref "C27") (pin "2") (pinfunction "2_2") (pintype "passive"))
      (node (ref "IC4") (pin "1") (pinfunction "BS_1") (pintype "bidirectional"))
    )
    (net (code "31") (name "Net-(IC4-EN)") (class "Default")
      (node (ref "IC4") (pin "4") (pinfunction "EN_4") (pintype "bidirectional"))
      (node (ref "R33") (pin "2") (pinfunction "2_2") (pintype "passive"))
    )
    (net (code "32") (name "Net-(IC4-FB)") (class "Default")
      (node (ref "C25") (pin "2") (pinfunction "2_2") (pintype "passive"))
      (node (ref "IC4") (pin "3") (pinfunction "FB_3") (pintype "bidirectional"))
      (node (ref "R31") (pin "1") (pinfunction "1_1") (pintype "passive"))
      (node (ref "R32") (pin "1") (pinfunction "1_1") (pintype "passive"))
    )
    (net (code "33") (name "Net-(IC5-CATHODE)") (class "Default")
      (node (ref "C18") (pin "2") (pinfunction "2_2") (pintype "passive"))
      (node (ref "IC5") (pin "1") (pinfunction "CATHODE_1") (pintype "bidirectional"))
      (node (ref "OPT1") (pin "2") (pinfunction "K_2") (pintype "bidirectional"))
      (node (ref "R15") (pin "1") (pinfunction "1_1") (pintype "passive"))
    )
    (net (code "34") (name "Net-(IC5-REF)") (class "Default")
      (node (ref "C17") (pin "1") (pinfunction "1_1") (pintype "passive"))
      (node (ref "C18") (pin "1") (pinfunction "1_1") (pintype "passive"))
      (node (ref "IC5") (pin "2") (pinfunction "REF_2") (pintype "bidirectional"))
      (node (ref "J2") (pin "1") (pinfunction "1_1") (pintype "passive"))
      (node (ref "R22") (pin "2") (pinfunction "2_2") (pintype "passive"))
      (node (ref "R23") (pin "2") (pinfunction "2_2") (pintype "passive"))
    )
    (net (code "35") (name "Net-(OPT1-A)") (class "Default")
      (node (ref "OPT1") (pin "1") (pinfunction "A_1") (pintype "bidirectional"))
      (node (ref "R35") (pin "2") (pinfunction "2_2") (pintype "passive"))
    )
    (net (code "36") (name "Net-(Q1-G)") (class "Default")
      (node (ref "GATE1_TP") (pin "TP") (pinfunction "TP_TP") (pintype "input"))
      (node (ref "Q1") (pin "1") (pinfunction "G_1") (pintype "bidirectional"))
      (node (ref "R2") (pin "2") (pinfunction "2_2") (pintype "passive"))
      (node (ref "R3") (pin "2") (pinfunction "2_2") (pintype "passive"))
    )
    (net (code "37") (name "Net-(Q2-G)") (class "Default")
      (node (ref "GATE2_TP") (pin "TP") (pinfunction "TP_TP") (pintype "input"))
      (node (ref "Q2") (pin "1") (pinfunction "G_1") (pintype "bidirectional"))
      (node (ref "R7") (pin "2") (pinfunction "2_2") (pintype "passive"))
      (node (ref "R8") (pin "2") (pinfunction "2_2") (pintype "passive"))
    )
    (net (code "38") (name "Net-(R21-Pad2)") (class "Default")
      (node (ref "R21") (pin "2") (pinfunction "2_2") (pintype "passive"))
      (node (ref "R22") (pin "1") (pinfunction "1_1") (pintype "passive"))
    )
    (net (code "39") (name "Net-(R23-Pad1)") (class "Default")
      (node (ref "R23") (pin "1") (pinfunction "1_1") (pintype "passive"))
      (node (ref "R24") (pin "2") (pinfunction "2_2") (pintype "passive"))
    )
    (net (code "40") (name "Net-(R24-Pad1)") (class "Default")
      (node (ref "R24") (pin "1") (pinfunction "1_1") (pintype "passive"))
      (node (ref "R25") (pin "2") (pinfunction "2_2") (pintype "passive"))
    )
    (net (code "41") (name "Net-(R26-Pad1)") (class "Default")
      (node (ref "R26") (pin "1") (pinfunction "1_1") (pintype "passive"))
      (node (ref "R27") (pin "2") (pinfunction "2_2") (pintype "passive"))
    )
    (net (code "42") (name "Net-(R27-Pad1)") (class "Default")
      (node (ref "R27") (pin "1") (pinfunction "1_1") (pintype "passive"))
      (node (ref "R28") (pin "2") (pinfunction "2_2") (pintype "passive"))
    )
    (net (code "43") (name "Net-(R28-Pad1)") (class "Default")
      (node (ref "R28") (pin "1") (pinfunction "1_1") (pintype "passive"))
      (node (ref "R29") (pin "2") (pinfunction "2_2") (pintype "passive"))
    )
    (net (code "44") (name "Net-(R29-Pad1)") (class "Default")
      (node (ref "R29") (pin "1") (pinfunction "1_1") (pintype "passive"))
      (node (ref "R30") (pin "2") (pinfunction "2_2") (pintype "passive"))
    )
    (net (code "45") (name "Net-(VR1-ADJ)") (class "Default")
      (node (ref "R10") (pin "1") (pinfunction "1_1") (pintype "passive"))
      (node (ref "R9") (pin "2") (pinfunction "2_2") (pintype "passive"))
      (node (ref "VR1") (pin "1") (pinfunction "ADJ_1") (pintype "input"))
    )
    (net (code "46") (name "OPTO-EMITT") (class "Default")
      (node (ref "IC2") (pin "1") (pinfunction "CTRL_1") (pintype "bidirectional"))
      (node (ref "OPT1") (pin "4") (pinfunction "C_4") (pintype "bidirectional"))
      (node (ref "R12") (pin "2") (pinfunction "2_2") (pintype "passive"))
    )
    (net (code "47") (name "PRE") (class "Default")
      (node (ref "C25") (pin "1") (pinfunction "1_1") (pintype "passive"))
      (node (ref "C28") (pin "2") (pinfunction "2_2") (pintype "passive"))
      (node (ref "C29") (pin "2") (pinfunction "2_2") (pintype "passive"))
      (node (ref "C30") (pin "2") (pinfunction "2_2") (pintype "passive"))
      (node (ref "L2") (pin "2") (pinfunction "P$2_2") (pintype "bidirectional"))
      (node (ref "MAINBUCK_TP") (pin "TP") (pinfunction "TP_TP") (pintype "input"))
      (node (ref "R32") (pin "2") (pinfunction "2_2") (pintype "passive"))
      (node (ref "VR1") (pin "3") (pinfunction "IN_3") (pintype "input"))
    )
    (net (code "48") (name "PWRGND") (class "Default")
      (node (ref "C21") (pin "2") (pinfunction "2_2") (pintype "passive"))
      (node (ref "C22") (pin "1") (pinfunction "1_1") (pintype "passive"))
      (node (ref "C23") (pin "1") (pinfunction "1_1") (pintype "passive"))
      (node (ref "C24") (pin "1") (pinfunction "1_1") (pintype "passive"))
      (node (ref "C32") (pin "1") (pinfunction "1_1") (pintype "passive"))
      (node (ref "C33") (pin "1") (pinfunction "1_1") (pintype "passive"))
      (node (ref "C34") (pin "2") (pinfunction "2_2") (pintype "passive"))
      (node (ref "C4") (pin "2") (pinfunction "2_2") (pintype "bidirectional"))
      (node (ref "C5") (pin "2") (pinfunction "2_2") (pintype "bidirectional"))
      (node (ref "C6") (pin "2") (pinfunction "-_2") (pintype "bidirectional"))
      (node (ref "C7") (pin "2") (pinfunction "-_2") (pintype "bidirectional"))
      (node (ref "D1") (pin "2") (pinfunction "A_2") (pintype "bidirectional"))
      (node (ref "D4") (pin "2") (pinfunction "A_2") (pintype "bidirectional"))
      (node (ref "D7") (pin "2") (pinfunction "A_2") (pintype "bidirectional"))
      (node (ref "HVLED") (pin "C") (pinfunction "C_C") (pintype "passive"))
      (node (ref "IC3") (pin "2") (pinfunction "GND_2") (pintype "bidirectional"))
      (node (ref "IC5") (pin "3") (pinfunction "ANODE_3") (pintype "bidirectional"))
      (node (ref "J1") (pin "1") (pinfunction "1_1") (pintype "bidirectional"))
      (node (ref "J2") (pin "2") (pinfunction "2_2") (pintype "passive"))
      (node (ref "PWRGND_TP") (pin "TP") (pinfunction "TP_TP") (pintype "input"))
      (node (ref "R19") (pin "2") (pinfunction "2_2") (pintype "passive"))
      (node (ref "R21") (pin "1") (pinfunction "1_1") (pintype "passive"))
      (node (ref "R36") (pin "1") (pinfunction "1_1") (pintype "passive"))
      (node (ref "T1") (pin "15") (pinfunction "15_15") (pintype "bidirectional"))
      (node (ref "T1.1") (pin "4") (pinfunction "4_4") (pintype "bidirectional"))
      (node (ref "VR2") (pin "1") (pinfunction "GND_1") (pintype "bidirectional"))
      (node (ref "Z3") (pin "2") (pinfunction "A_2") (pintype "bidirectional"))
    )
    (net (code "49") (name "RECT") (class "Default")
      (node (ref "D2") (pin "1") (pinfunction "K_1_1") (pintype "bidirectional"))
      (node (ref "D2") (pin "3") (pinfunction "K_2_3") (pintype "bidirectional"))
      (node (ref "D3") (pin "1") (pinfunction "K_1_1") (pintype "bidirectional"))
      (node (ref "D3") (pin "3") (pinfunction "K_2_3") (pintype "bidirectional"))
      (node (ref "L1") (pin "1") (pinfunction "1_1") (pintype "bidirectional"))
    )
    (net (code "50") (name "REG") (class "Default")
      (node (ref "13.75V") (pin "A") (pinfunction "A_A") (pintype "passive"))
      (node (ref "13.75V_TP") (pin "TP") (pinfunction "TP_TP") (pintype "input"))
      (node (ref "C10") (pin "1") (pinfunction "1_1") (pintype "passive"))
      (node (ref "C14") (pin "1") (pinfunction "1_1") (pintype "passive"))
      (node (ref "C15") (pin "1") (pinfunction "1_1") (pintype "passive"))
      (node (ref "C31") (pin "2") (pinfunction "2_2") (pintype "passive"))
      (node (ref "C9") (pin "1") (pinfunction "1_1") (pintype "passive"))
      (node (ref "IC1") (pin "6") (pinfunction "VDD_6") (pintype "bidirectional"))
      (node (ref "IC2") (pin "8") (pinfunction "VDD_8") (pintype "bidirectional"))
      (node (ref "R10") (pin "2") (pinfunction "2_2") (pintype "passive"))
      (node (ref "R12") (pin "1") (pinfunction "1_1") (pintype "passive"))
      (node (ref "R4") (pin "2") (pinfunction "2_2") (pintype "passive"))
      (node (ref "VR1") (pin "4") (pinfunction "OUT_4") (pintype "passive"))
    )
    (net (code "51") (name "REG5V") (class "Default")
      (node (ref "5VLED") (pin "A") (pinfunction "A_A") (pintype "passive"))
      (node (ref "AUX5V_TP") (pin "TP") (pinfunction "TP_TP") (pintype "input"))
      (node (ref "C33") (pin "2") (pinfunction "2_2") (pintype "passive"))
      (node (ref "R35") (pin "1") (pinfunction "1_1") (pintype "passive"))
      (node (ref "VR2") (pin "2") (pinfunction "VOUT_2") (pintype "bidirectional"))
    )
    (net (code "52") (name "TRANS1") (class "Default")
      (node (ref "D1") (pin "1") (pinfunction "K_1_1") (pintype "bidirectional"))
      (node (ref "D1") (pin "3") (pinfunction "K_2_3") (pintype "bidirectional"))
      (node (ref "D2") (pin "2") (pinfunction "A_2") (pintype "bidirectional"))
      (node (ref "T1") (pin "11") (pinfunction "11_11") (pintype "bidirectional"))
      (node (ref "T1.1") (pin "8") (pinfunction "8_8") (pintype "bidirectional"))
    )
    (net (code "53") (name "TRANS2") (class "Default")
      (node (ref "D3") (pin "2") (pinfunction "A_2") (pintype "bidirectional"))
      (node (ref "D4") (pin "1") (pinfunction "K_1_1") (pintype "bidirectional"))
      (node (ref "D4") (pin "3") (pinfunction "K_2_3") (pintype "bidirectional"))
      (node (ref "T1") (pin "9") (pinfunction "9_9") (pintype "bidirectional"))
      (node (ref "T1.1") (pin "14") (pinfunction "14_14") (pintype "bidirectional"))
    )
    (net (code "54") (name "VCCIN") (class "Default")
      (node (ref "C1") (pin "1") (pinfunction "+_1") (pintype "bidirectional"))
      (node (ref "C11") (pin "2") (pinfunction "2_2") (pintype "passive"))
      (node (ref "C12") (pin "1") (pinfunction "+_1") (pintype "bidirectional"))
      (node (ref "C13") (pin "1") (pinfunction "+_1") (pintype "bidirectional"))
      (node (ref "C2") (pin "1") (pinfunction "+_1") (pintype "bidirectional"))
      (node (ref "C26") (pin "1") (pinfunction "1_1") (pintype "passive"))
      (node (ref "C3") (pin "2") (pinfunction "2_2") (pintype "passive"))
      (node (ref "C36") (pin "2") (pinfunction "2_2") (pintype "passive"))
      (node (ref "C8") (pin "1") (pinfunction "1_1") (pintype "passive"))
      (node (ref "IC4") (pin "5") (pinfunction "IN_5") (pintype "bidirectional"))
      (node (ref "INPUT") (pin "1") (pinfunction "1_1") (pintype "bidirectional"))
      (node (ref "R33") (pin "1") (pinfunction "1_1") (pintype "passive"))
      (node (ref "R37") (pin "2") (pinfunction "2_2") (pintype "passive"))
      (node (ref "R38") (pin "2") (pinfunction "2_2") (pintype "passive"))
      (node (ref "T1") (pin "4") (pinfunction "4_4") (pintype "bidirectional"))
      (node (ref "T1") (pin "5") (pinfunction "5_5") (pintype "bidirectional"))
      (node (ref "T1.1") (pin "7") (pinfunction "7_7") (pintype "bidirectional"))
    )
    (net (code "55") (name "unconnected-(T1-Pad10)") (class "Default")
      (node (ref "T1") (pin "10") (pinfunction "10_10") (pintype "bidirectional"))
    )
    (net (code "56") (name "unconnected-(T1-Pad12)") (class "Default")
      (node (ref "T1") (pin "12") (pinfunction "12_12") (pintype "bidirectional"))
    )
    (net (code "57") (name "unconnected-(T1-Pad13)") (class "Default")
      (node (ref "T1") (pin "13") (pinfunction "13_13") (pintype "bidirectional"))
    )
    (net (code "58") (name "unconnected-(T1-Pad14)") (class "Default")
      (node (ref "T1") (pin "14") (pinfunction "14_14") (pintype "bidirectional"))
    )
    (net (code "59") (name "unconnected-(T1.1-Pad6)") (class "Default")
      (node (ref "T1.1") (pin "6") (pinfunction "6_6") (pintype "bidirectional"))
    )
    (net (code "60") (name "unconnected-(T1.1-Pad10)") (class "Default")
      (node (ref "T1.1") (pin "10") (pinfunction "10_10") (pintype "bidirectional"))
    )
    (net (code "61") (name "unconnected-(T1.1-Pad12)") (class "Default")
      (node (ref "T1.1") (pin "12") (pinfunction "12_12") (pintype "bidirectional"))
    )
  )
)
